# FLEX_MCU_CONFIG.net
KiCad netlist of a schematic drawn in Altium Designer
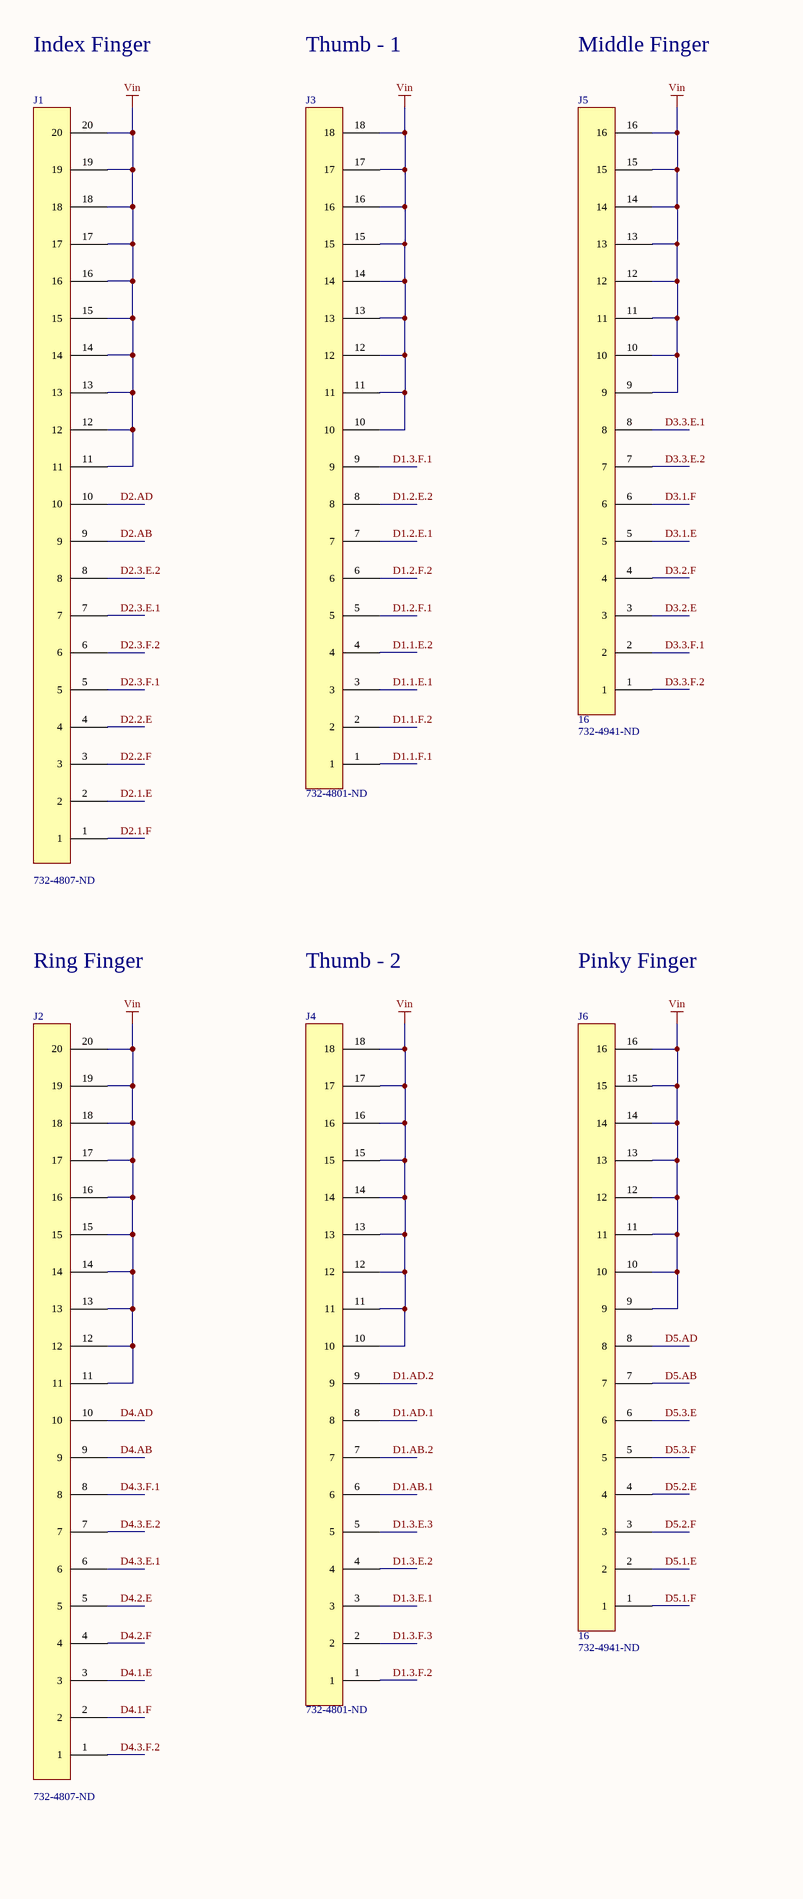
[diagram p0: FLEX_MCU_CONFIG.SchDoc, left]
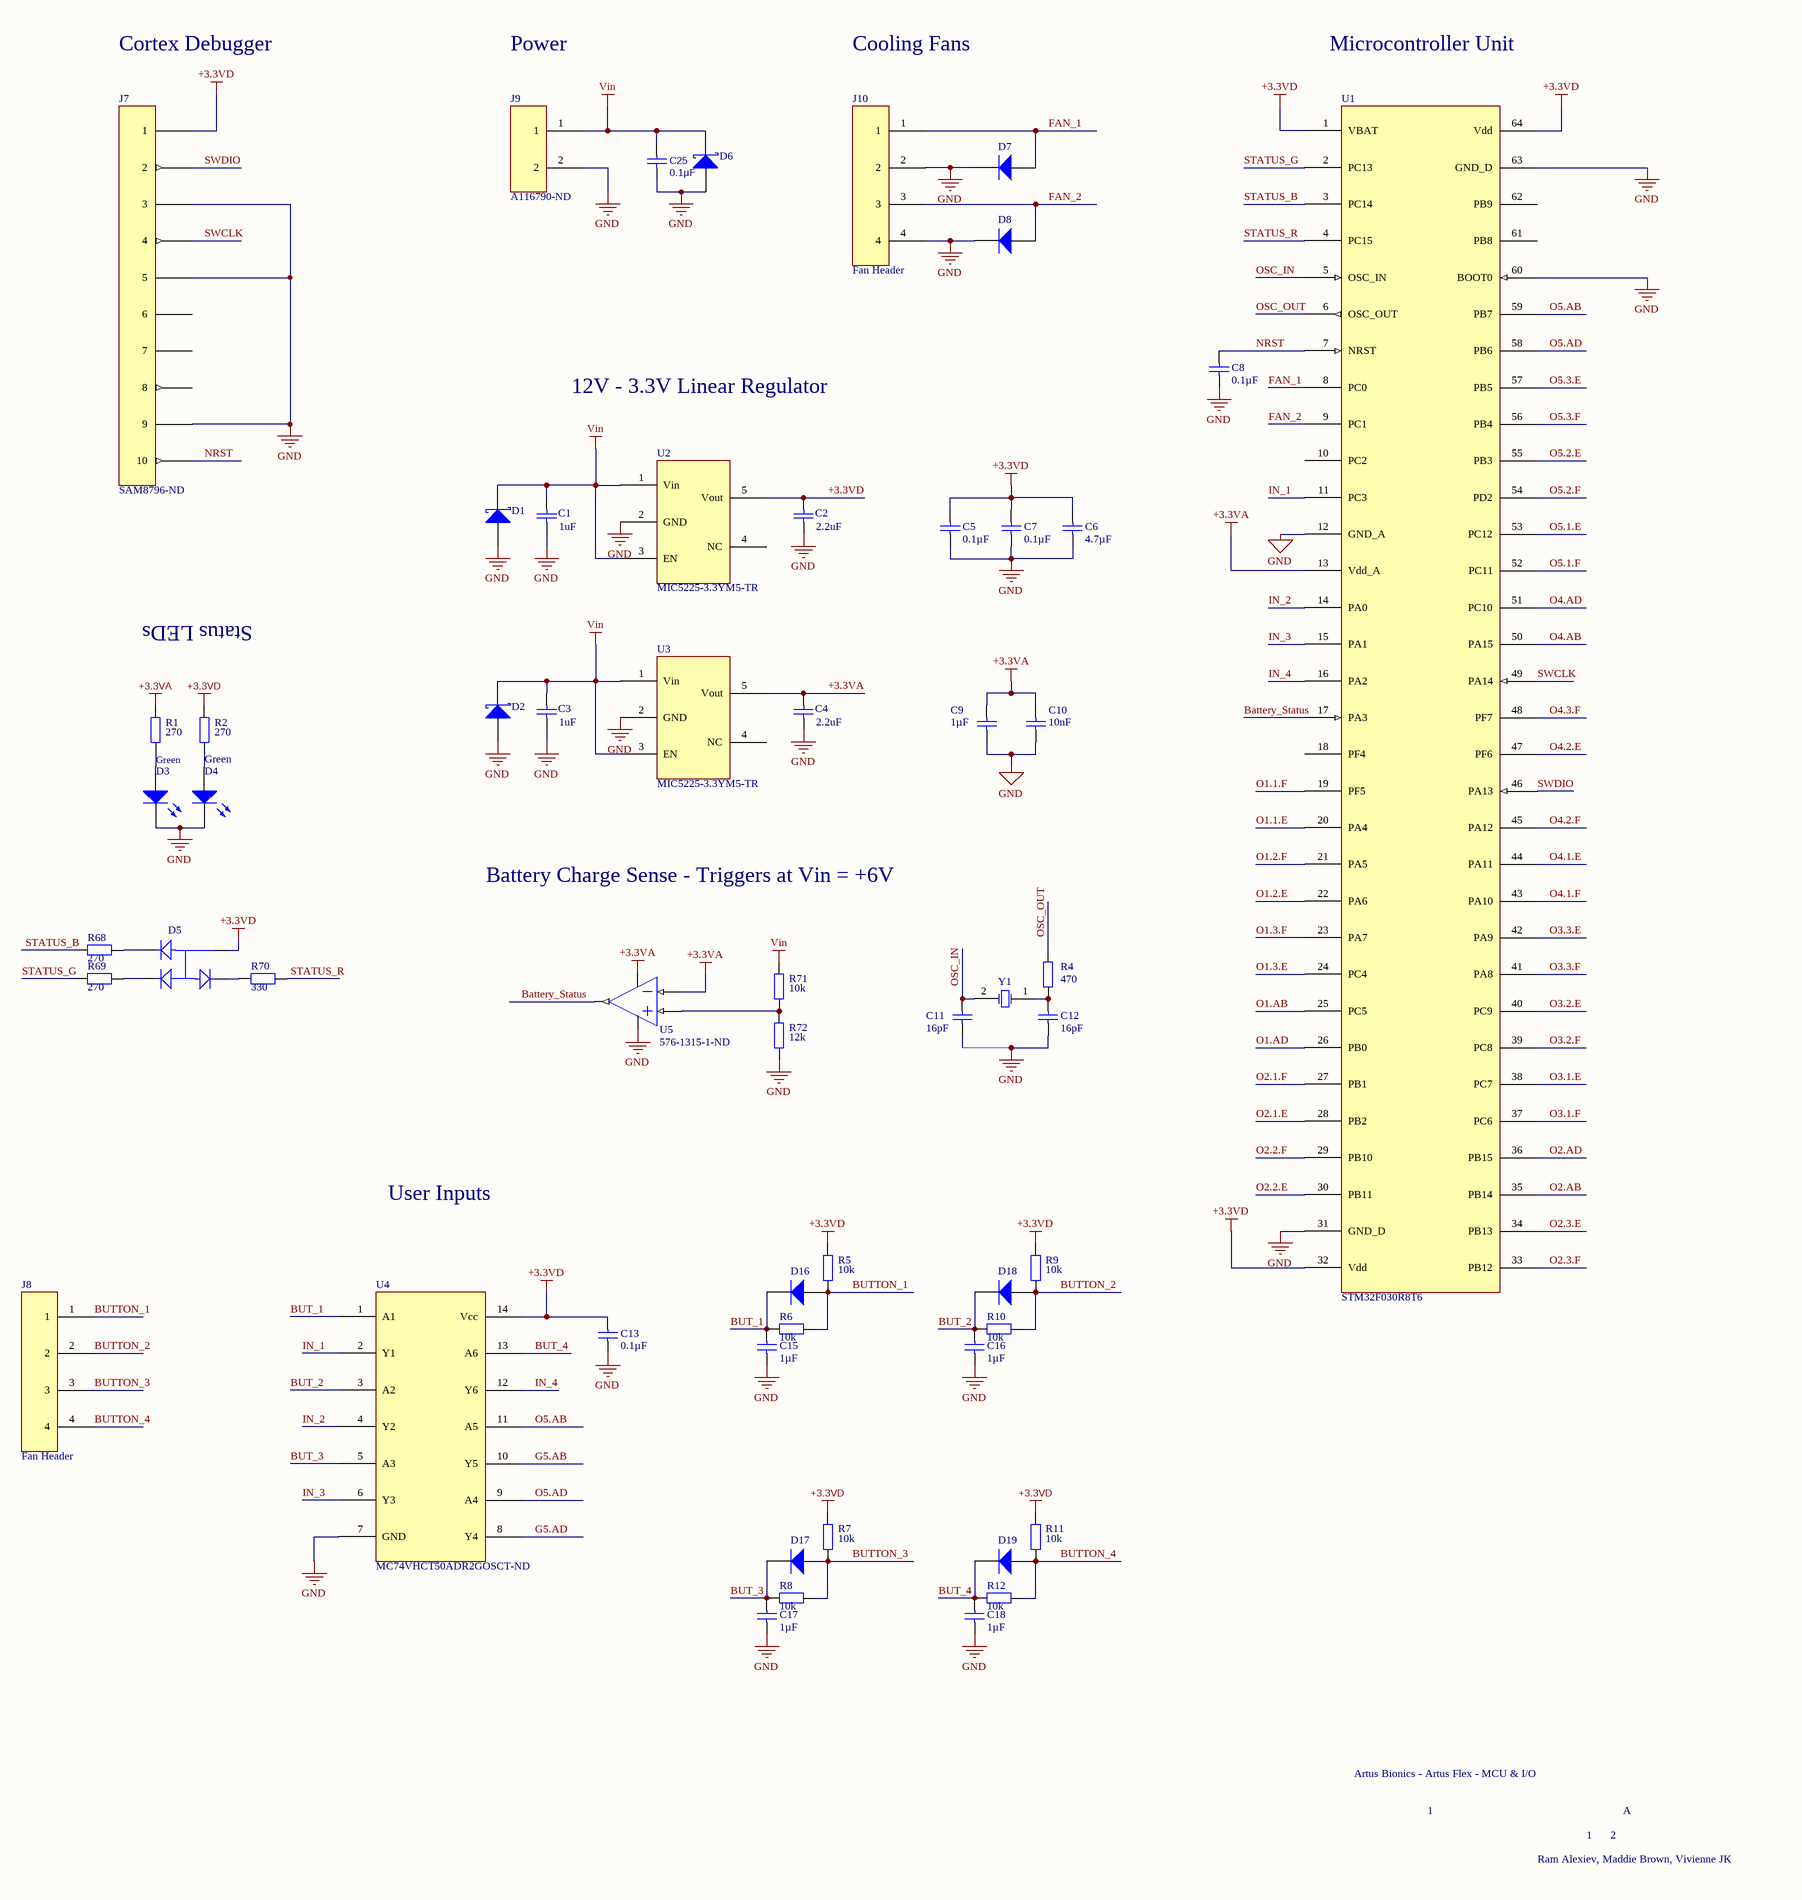
[diagram p1: FLEX_MCU_CONFIG.SchDoc, right]

(export (version "E")
  (design (tool "Eeschema 10.0.6"))
  (components
    (comp (ref "C1")
      (value "1uF")
      (footprint "TDK C-Series (1608)")
      (description "Capacitor")
      (fields (field (name "PUBLISHER") "Altium Limited"))
      (libsource (lib "Miscellaneous Devices") (part "Cap"))
    )
    (comp (ref "C2")
      (value "2.2uF")
      (footprint "TDK C-Series (1608)")
      (description "Capacitor")
      (fields (field (name "PUBLISHER") "Altium Limited"))
      (libsource (lib "Miscellaneous Devices") (part "Cap"))
    )
    (comp (ref "C3")
      (value "1uF")
      (footprint "TDK C-Series (1608)")
      (description "Capacitor")
      (fields (field (name "PUBLISHER") "Altium Limited"))
      (libsource (lib "Miscellaneous Devices") (part "Cap"))
    )
    (comp (ref "C4")
      (value "2.2uF")
      (footprint "TDK C-Series (1608)")
      (description "Capacitor")
      (fields (field (name "PUBLISHER") "Altium Limited"))
      (libsource (lib "Miscellaneous Devices") (part "Cap"))
    )
    (comp (ref "C5")
      (value "0.1µF")
      (footprint "TDK C-Series (1608)")
      (description "Capacitor")
      (fields (field (name "PUBLISHER") "Altium Limited"))
      (libsource (lib "Miscellaneous Devices") (part "Cap"))
    )
    (comp (ref "C6")
      (value "4.7µF")
      (footprint "TDK C-Series (1608)")
      (description "Capacitor")
      (fields (field (name "Comment") "Cap") (field (name "PUBLISHER") "Altium Limited"))
      (libsource (lib "Miscellaneous Devices") (part "Cap"))
    )
    (comp (ref "C7")
      (value "0.1µF")
      (footprint "TDK C-Series (1608)")
      (description "Capacitor")
      (fields (field (name "PUBLISHER") "Altium Limited"))
      (libsource (lib "Miscellaneous Devices") (part "Cap"))
    )
    (comp (ref "C8")
      (value "0.1µF")
      (footprint "TDK C-Series (1608)")
      (description "Capacitor")
      (fields (field (name "PUBLISHER") "Altium Limited"))
      (libsource (lib "Miscellaneous Devices") (part "Cap"))
    )
    (comp (ref "C9")
      (value "1µF")
      (footprint "TDK C-Series (1608)")
      (description "Capacitor")
      (fields (field (name "PUBLISHER") "Altium Limited"))
      (libsource (lib "Miscellaneous Devices") (part "Cap"))
    )
    (comp (ref "C10")
      (value "10nF")
      (footprint "TDK C-Series (1608)")
      (description "Capacitor")
      (fields (field (name "PUBLISHER") "Altium Limited"))
      (libsource (lib "Miscellaneous Devices") (part "Cap"))
    )
    (comp (ref "C11")
      (value "16pF")
      (footprint "Johanson S-Series (1608)")
      (description "Capacitor")
      (fields (field (name "PUBLISHER") "Altium Limited"))
      (libsource (lib "Miscellaneous Devices") (part "Cap"))
    )
    (comp (ref "C12")
      (value "16pF")
      (footprint "Johanson S-Series (1608)")
      (description "Capacitor")
      (fields (field (name "PUBLISHER") "Altium Limited"))
      (libsource (lib "Miscellaneous Devices") (part "Cap"))
    )
    (comp (ref "C13")
      (value "0.1µF")
      (footprint "TDK C-Series (1608)")
      (description "Capacitor")
      (fields (field (name "Comment") "Cap") (field (name "PUBLISHER") "Altium Limited"))
      (libsource (lib "Miscellaneous Devices") (part "Cap"))
    )
    (comp (ref "C15")
      (value "1µF")
      (footprint "TDK C-Series (1608)")
      (description "Capacitor")
      (fields (field (name "Comment") "Cap") (field (name "PUBLISHER") "Altium Limited"))
      (libsource (lib "Miscellaneous Devices") (part "Cap"))
    )
    (comp (ref "C16")
      (value "1µF")
      (footprint "TDK C-Series (1608)")
      (description "Capacitor")
      (fields (field (name "Comment") "Cap") (field (name "PUBLISHER") "Altium Limited"))
      (libsource (lib "Miscellaneous Devices") (part "Cap"))
    )
    (comp (ref "C17")
      (value "1µF")
      (footprint "TDK C-Series (1608)")
      (description "Capacitor")
      (fields (field (name "Comment") "Cap") (field (name "PUBLISHER") "Altium Limited"))
      (libsource (lib "Miscellaneous Devices") (part "Cap"))
    )
    (comp (ref "C18")
      (value "1µF")
      (footprint "TDK C-Series (1608)")
      (description "Capacitor")
      (fields (field (name "Comment") "Cap") (field (name "PUBLISHER") "Altium Limited"))
      (libsource (lib "Miscellaneous Devices") (part "Cap"))
    )
    (comp (ref "C25")
      (value "0.1µF")
      (footprint "TDK C-Series (1608)")
      (description "Capacitor")
      (fields (field (name "PUBLISHER") "Altium Limited"))
      (libsource (lib "Miscellaneous Devices") (part "Cap"))
    )
    (comp (ref "D1")
      (value "~")
      (footprint "Diode_TVS")
      (description "Schottky Rectifier")
      (fields (field (name "PUBLISHER") "Altium Limited"))
      (libsource (lib "Miscellaneous Devices") (part "Diode 10TQ035"))
    )
    (comp (ref "D2")
      (value "~")
      (footprint "Diode_TVS")
      (description "Schottky Rectifier")
      (fields (field (name "PUBLISHER") "Altium Limited"))
      (libsource (lib "Miscellaneous Devices") (part "Diode 10TQ035"))
    )
    (comp (ref "D3")
      (value "LTST-C193KGKT-5A")
      (footprint "Lite-On LTST-C193K-Series (1608)")
      (description "Typical INFRARED GaAs LED")
      (fields (field (name "PUBLISHER") "Altium Limited"))
      (libsource (lib "Miscellaneous Devices") (part "LED0"))
    )
    (comp (ref "D4")
      (value "LTST-C193KGKT-5A")
      (footprint "Lite-On LTST-C193K-Series (1608)")
      (description "Typical INFRARED GaAs LED")
      (fields (field (name "PUBLISHER") "Altium Limited"))
      (libsource (lib "Miscellaneous Devices") (part "LED0"))
    )
    (comp (ref "D5")
      (value "Cree CLVBA-FKA-CAEDH8BBB7A363")
      (footprint "Cree CLVBA-FKA-Series (4-SOJ)")
      (description "RGB LED")
      (libsource (lib "BMS_2017 Core") (part "Cree CLVBA-FKA-CAEDH8BBB7A363"))
    )
    (comp (ref "D6")
      (value "Diode BAT17")
      (footprint "Diode_TVS")
      (description "Silicon RF Schottky Diode for Mixer Applications in the VHF/UHF Range")
      (fields (field (name "PUBLISHER") "Altium Limited"))
      (libsource (lib "Miscellaneous Devices") (part "Diode BAT17"))
    )
    (comp (ref "D7")
      (value "Diode 1N4006")
      (footprint "Diode_Shottky")
      (description "1 Amp General Purpose Rectifier")
      (fields (field (name "PUBLISHER") "Altium Limited"))
      (libsource (lib "Miscellaneous Devices") (part "Diode 1N4006"))
    )
    (comp (ref "D8")
      (value "Diode 1N4006")
      (footprint "Diode_Shottky")
      (description "1 Amp General Purpose Rectifier")
      (fields (field (name "PUBLISHER") "Altium Limited"))
      (libsource (lib "Miscellaneous Devices") (part "Diode 1N4006"))
    )
    (comp (ref "D16")
      (value "de")
      (footprint "Diode_Shottky")
      (description "Default Diode")
      (fields (field (name "PUBLISHER") "Altium Limited"))
      (libsource (lib "Miscellaneous Devices") (part "Diode"))
    )
    (comp (ref "D17")
      (value "de")
      (footprint "Diode_Shottky")
      (description "Default Diode")
      (fields (field (name "PUBLISHER") "Altium Limited"))
      (libsource (lib "Miscellaneous Devices") (part "Diode"))
    )
    (comp (ref "D18")
      (value "de")
      (footprint "Diode_Shottky")
      (description "Default Diode")
      (fields (field (name "PUBLISHER") "Altium Limited"))
      (libsource (lib "Miscellaneous Devices") (part "Diode"))
    )
    (comp (ref "D19")
      (value "de")
      (footprint "Diode_Shottky")
      (description "Default Diode")
      (fields (field (name "PUBLISHER") "Altium Limited"))
      (libsource (lib "Miscellaneous Devices") (part "Diode"))
    )
    (comp (ref "J1")
      (value "20 Pin Header")
      (footprint "20PIN_UP_CONNECTOR")
      (description "20 position header")
      (fields (field (name "SUPPLIER PART NUMBER 1") "732-4807-ND"))
      (libsource (lib "Schematics Library") (part "20 Pin Header"))
    )
    (comp (ref "J2")
      (value "20 Pin Header")
      (footprint "20PIN_UP_CONNECTOR")
      (description "20 position header")
      (fields (field (name "SUPPLIER PART NUMBER 1") "732-4807-ND"))
      (libsource (lib "Schematics Library") (part "20 Pin Header"))
    )
    (comp (ref "J3")
      (value "18 Pin Header")
      (footprint "18PIN_UP_CONNECTOR")
      (description "18 Position Header")
      (fields (field (name "SUPPLIER PART NUMBER 1") "732-4801-ND"))
      (libsource (lib "Schematics Library") (part "18 Pin Header"))
    )
    (comp (ref "J4")
      (value "18 Pin Header")
      (footprint "18PIN_UP_CONNECTOR")
      (description "18 Position Header")
      (fields (field (name "SUPPLIER PART NUMBER 1") "732-4801-ND"))
      (libsource (lib "Schematics Library") (part "18 Pin Header"))
    )
    (comp (ref "J5")
      (value "16")
      (description "16 Position header")
      (fields (field (name "SUPPLIER PART NUMBER 1") "732-4941-ND"))
      (libsource (lib "Schematics Library") (part "16"))
    )
    (comp (ref "J6")
      (value "16")
      (description "16 Position header")
      (fields (field (name "SUPPLIER PART NUMBER 1") "732-4941-ND"))
      (libsource (lib "Schematics Library") (part "16"))
    )
    (comp (ref "J7")
      (value "Cortex Debugger")
      (footprint "Samtec FTSH-105-01-L-DV-K")
      (description "Header")
      (fields (field (name "SUPPLIER PART NUMBER 2") "SAM8796-ND"))
      (libsource (lib "Schematics Library") (part "Cortex Debugger"))
    )
    (comp (ref "J8") (value "Fan Header") (libsource (lib "Schematics Library") (part "Fan Header")))
    (comp (ref "J9")
      (value "Power Header")
      (footprint "2PIN_TERMINAL_BLOCK")
      (fields (field (name "SUPPLIER PART NUMBER 1") "A116790-ND"))
      (libsource (lib "Schematics Library") (part "Power Header"))
    )
    (comp (ref "J10") (value "Fan Header") (libsource (lib "Schematics Library") (part "Fan Header")))
    (comp (ref "R1")
      (value "270")
      (footprint "Panasonic ERJ-Series (1608)")
      (description "Resistor")
      (fields (field (name "PUBLISHER") "Altium Limited"))
      (libsource (lib "Miscellaneous Devices") (part "Res2"))
    )
    (comp (ref "R2")
      (value "270")
      (footprint "Panasonic ERJ-Series (1608)")
      (description "Resistor")
      (fields (field (name "PUBLISHER") "Altium Limited"))
      (libsource (lib "Miscellaneous Devices") (part "Res2"))
    )
    (comp (ref "R4")
      (value "470")
      (footprint "Panasonic ERJ-Series (1608)")
      (description "Resistor")
      (fields (field (name "PUBLISHER") "Altium Limited"))
      (libsource (lib "Miscellaneous Devices") (part "Res2"))
    )
    (comp (ref "R5")
      (value "10k")
      (footprint "Panasonic ERJ-Series (1608)")
      (description "Resistor")
      (fields (field (name "PUBLISHER") "Altium Limited"))
      (libsource (lib "") (part "Res2_1"))
    )
    (comp (ref "R6")
      (value "10k")
      (footprint "Panasonic ERJ-Series (1608)")
      (description "Resistor")
      (fields (field (name "PUBLISHER") "Altium Limited"))
      (libsource (lib "Miscellaneous Devices") (part "Res2"))
    )
    (comp (ref "R7")
      (value "10k")
      (footprint "Panasonic ERJ-Series (1608)")
      (description "Resistor")
      (fields (field (name "PUBLISHER") "Altium Limited"))
      (libsource (lib "") (part "Res2_1"))
    )
    (comp (ref "R8")
      (value "10k")
      (footprint "Panasonic ERJ-Series (1608)")
      (description "Resistor")
      (fields (field (name "PUBLISHER") "Altium Limited"))
      (libsource (lib "Miscellaneous Devices") (part "Res2"))
    )
    (comp (ref "R9")
      (value "10k")
      (footprint "Panasonic ERJ-Series (1608)")
      (description "Resistor")
      (fields (field (name "PUBLISHER") "Altium Limited"))
      (libsource (lib "") (part "Res2_1"))
    )
    (comp (ref "R10")
      (value "10k")
      (footprint "Panasonic ERJ-Series (1608)")
      (description "Resistor")
      (fields (field (name "PUBLISHER") "Altium Limited"))
      (libsource (lib "Miscellaneous Devices") (part "Res2"))
    )
    (comp (ref "R11")
      (value "10k")
      (footprint "Panasonic ERJ-Series (1608)")
      (description "Resistor")
      (fields (field (name "PUBLISHER") "Altium Limited"))
      (libsource (lib "") (part "Res2_1"))
    )
    (comp (ref "R12")
      (value "10k")
      (footprint "Panasonic ERJ-Series (1608)")
      (description "Resistor")
      (fields (field (name "PUBLISHER") "Altium Limited"))
      (libsource (lib "Miscellaneous Devices") (part "Res2"))
    )
    (comp (ref "R68")
      (value "270")
      (footprint "Panasonic ERJ-Series (1608)")
      (description "Resistor")
      (fields (field (name "PUBLISHER") "Altium Limited"))
      (libsource (lib "") (part "Res2_2"))
    )
    (comp (ref "R69")
      (value "270")
      (footprint "Panasonic ERJ-Series (1608)")
      (description "Resistor")
      (fields (field (name "PUBLISHER") "Altium Limited"))
      (libsource (lib "") (part "Res2_2"))
    )
    (comp (ref "R70")
      (value "330")
      (footprint "Panasonic ERJ-Series (1608)")
      (description "Resistor")
      (fields (field (name "PUBLISHER") "Altium Limited"))
      (libsource (lib "") (part "Res2_2"))
    )
    (comp (ref "R71")
      (value "10k")
      (footprint "Panasonic ERJ-Series (1608)")
      (description "Resistor")
      (fields (field (name "PUBLISHER") "Altium Limited"))
      (libsource (lib "") (part "Res2_1"))
    )
    (comp (ref "R72")
      (value "12k")
      (footprint "Panasonic ERJ-Series (1608)")
      (description "Resistor")
      (fields (field (name "PUBLISHER") "Altium Limited"))
      (libsource (lib "") (part "Res2_1"))
    )
    (comp (ref "U1")
      (value "STM32F030R8T6")
      (description "MCU")
      (libsource (lib "Schematics Library") (part "STM32F030R8T6"))
    )
    (comp (ref "U2")
      (value "MIC5225-3.3YM5-TR")
      (footprint "LINEAR REGULATOR SOT95P280X145-5N")
      (description "12V-3.3V Linear Regulator")
      (libsource (lib "Schematics Library") (part "MIC5225-3.3YM5-TR"))
    )
    (comp (ref "U3")
      (value "MIC5225-3.3YM5-TR")
      (footprint "LINEAR REGULATOR SOT95P280X145-5N")
      (description "12V-3.3V Linear Regulator")
      (libsource (lib "Schematics Library") (part "MIC5225-3.3YM5-TR"))
    )
    (comp (ref "U4")
      (value "MC74VHCT50A")
      (description "6-Channel CMOS Buffer")
      (fields (field (name "SUPPLIER PART NUMBER 1") "MC74VHCT50ADR2GOSCT-ND"))
      (libsource (lib "Schematics Library") (part "MC74VHCT50A"))
    )
    (comp (ref "U5")
      (value "TSV991ILT")
      (footprint "LINEAR REGULATOR SOT95P280X145-5N")
      (description "20MHz Op-Amp")
      (fields (field (name "SUPPLIER PART NUMBER 1") "576-1315-1-ND"))
      (libsource (lib "FSM_2017") (part "STMicroelectronics TSV991ILT"))
    )
    (comp (ref "Y1")
      (value "~")
      (footprint "Abracon ABM3-8.000MHZ-D2Y-T (2-DFN)")
      (description "Crystal Oscillator")
      (fields (field (name "PUBLISHER") "Altium Limited"))
      (libsource (lib "Miscellaneous Devices") (part "XTAL"))
    )
  )
  (nets
    (net (code "1") (name "+3.3VA") (class "Default")
      (node (ref "C10") (pin "2") (pinfunction "2_2") (pintype "passive"))
      (node (ref "C4") (pin "2") (pinfunction "2_2") (pintype "passive"))
      (node (ref "C9") (pin "2") (pinfunction "2_2") (pintype "passive"))
      (node (ref "R1") (pin "2") (pinfunction "2_2") (pintype "passive"))
      (node (ref "U1") (pin "13") (pinfunction "Vdd_A_13") (pintype "power_in"))
      (node (ref "U3") (pin "5") (pinfunction "Vout_5") (pintype "passive"))
      (node (ref "U5") (pin "2") (pinfunction "VCC-_2") (pintype "power_in"))
      (node (ref "U5") (pin "4") (pinfunction "IN-_4") (pintype "input"))
    )
    (net (code "2") (name "+3.3VD") (class "Default")
      (node (ref "C13") (pin "2") (pinfunction "2_2") (pintype "passive"))
      (node (ref "C2") (pin "2") (pinfunction "2_2") (pintype "passive"))
      (node (ref "C5") (pin "2") (pinfunction "2_2") (pintype "passive"))
      (node (ref "C6") (pin "2") (pinfunction "2_2") (pintype "passive"))
      (node (ref "C7") (pin "2") (pinfunction "2_2") (pintype "passive"))
      (node (ref "D5") (pin "2") (pinfunction "COMMON_ANODE_2") (pintype "passive"))
      (node (ref "J7") (pin "1") (pinfunction "1_1") (pintype "power_in"))
      (node (ref "R11") (pin "1") (pinfunction "1_1") (pintype "passive"))
      (node (ref "R2") (pin "2") (pinfunction "2_2") (pintype "passive"))
      (node (ref "R5") (pin "1") (pinfunction "1_1") (pintype "passive"))
      (node (ref "R7") (pin "1") (pinfunction "1_1") (pintype "passive"))
      (node (ref "R9") (pin "1") (pinfunction "1_1") (pintype "passive"))
      (node (ref "U1") (pin "1") (pinfunction "VBAT_1") (pintype "power_in"))
      (node (ref "U1") (pin "32") (pinfunction "Vdd_32") (pintype "power_in"))
      (node (ref "U1") (pin "64") (pinfunction "Vdd_64") (pintype "power_in"))
      (node (ref "U2") (pin "5") (pinfunction "Vout_5") (pintype "passive"))
      (node (ref "U4") (pin "14") (pinfunction "Vcc_14") (pintype "power_in"))
    )
    (net (code "3") (name "/BUTTON_1") (class "Default")
      (node (ref "D16") (pin "1") (pinfunction "A_1") (pintype "passive"))
      (node (ref "J8") (pin "1") (pinfunction "1_1") (pintype "power_in"))
      (node (ref "R5") (pin "2") (pinfunction "2_2") (pintype "passive"))
      (node (ref "R6") (pin "2") (pinfunction "2_2") (pintype "passive"))
    )
    (net (code "4") (name "/BUTTON_2") (class "Default")
      (node (ref "D18") (pin "1") (pinfunction "A_1") (pintype "passive"))
      (node (ref "J8") (pin "2") (pinfunction "2_2") (pintype "power_in"))
      (node (ref "R10") (pin "2") (pinfunction "2_2") (pintype "passive"))
      (node (ref "R9") (pin "2") (pinfunction "2_2") (pintype "passive"))
    )
    (net (code "5") (name "/BUTTON_3") (class "Default")
      (node (ref "D17") (pin "1") (pinfunction "A_1") (pintype "passive"))
      (node (ref "J8") (pin "3") (pinfunction "3_3") (pintype "power_in"))
      (node (ref "R7") (pin "2") (pinfunction "2_2") (pintype "passive"))
      (node (ref "R8") (pin "2") (pinfunction "2_2") (pintype "passive"))
    )
    (net (code "6") (name "/BUTTON_4") (class "Default")
      (node (ref "D19") (pin "1") (pinfunction "A_1") (pintype "passive"))
      (node (ref "J8") (pin "4") (pinfunction "4_4") (pintype "power_in"))
      (node (ref "R11") (pin "2") (pinfunction "2_2") (pintype "passive"))
      (node (ref "R12") (pin "2") (pinfunction "2_2") (pintype "passive"))
    )
    (net (code "7") (name "/BUT_1") (class "Default")
      (node (ref "C15") (pin "2") (pinfunction "2_2") (pintype "passive"))
      (node (ref "D16") (pin "2") (pinfunction "K_2") (pintype "passive"))
      (node (ref "R6") (pin "1") (pinfunction "1_1") (pintype "passive"))
      (node (ref "U4") (pin "1") (pinfunction "A1_1") (pintype "power_in"))
    )
    (net (code "8") (name "/BUT_2") (class "Default")
      (node (ref "C16") (pin "2") (pinfunction "2_2") (pintype "passive"))
      (node (ref "D18") (pin "2") (pinfunction "K_2") (pintype "passive"))
      (node (ref "R10") (pin "1") (pinfunction "1_1") (pintype "passive"))
      (node (ref "U4") (pin "3") (pinfunction "A2_3") (pintype "power_in"))
    )
    (net (code "9") (name "/BUT_3") (class "Default")
      (node (ref "C17") (pin "2") (pinfunction "2_2") (pintype "passive"))
      (node (ref "D17") (pin "2") (pinfunction "K_2") (pintype "passive"))
      (node (ref "R8") (pin "1") (pinfunction "1_1") (pintype "passive"))
      (node (ref "U4") (pin "5") (pinfunction "A3_5") (pintype "power_in"))
    )
    (net (code "10") (name "/BUT_4") (class "Default")
      (node (ref "C18") (pin "2") (pinfunction "2_2") (pintype "passive"))
      (node (ref "D19") (pin "2") (pinfunction "K_2") (pintype "passive"))
      (node (ref "R12") (pin "1") (pinfunction "1_1") (pintype "passive"))
      (node (ref "U4") (pin "13") (pinfunction "A6_13") (pintype "power_in"))
    )
    (net (code "11") (name "/Battery_Status") (class "Default")
      (node (ref "U1") (pin "17") (pinfunction "PA3_17") (pintype "input"))
      (node (ref "U5") (pin "1") (pinfunction "OUT_1") (pintype "output"))
    )
    (net (code "12") (name "/D1.1.E.1") (class "Default")
      (node (ref "J3") (pin "3") (pinfunction "3_3") (pintype "power_in"))
    )
    (net (code "13") (name "/D1.1.E.2") (class "Default")
      (node (ref "J3") (pin "4") (pinfunction "4_4") (pintype "power_in"))
    )
    (net (code "14") (name "/D1.1.F.1") (class "Default")
      (node (ref "J3") (pin "1") (pinfunction "1_1") (pintype "power_in"))
    )
    (net (code "15") (name "/D1.1.F.2") (class "Default")
      (node (ref "J3") (pin "2") (pinfunction "2_2") (pintype "power_in"))
    )
    (net (code "16") (name "/D1.2.E.1") (class "Default")
      (node (ref "J3") (pin "7") (pinfunction "7_7") (pintype "power_in"))
    )
    (net (code "17") (name "/D1.2.E.2") (class "Default")
      (node (ref "J3") (pin "8") (pinfunction "8_8") (pintype "power_in"))
    )
    (net (code "18") (name "/D1.2.F.1") (class "Default")
      (node (ref "J3") (pin "5") (pinfunction "5_5") (pintype "power_in"))
    )
    (net (code "19") (name "/D1.2.F.2") (class "Default")
      (node (ref "J3") (pin "6") (pinfunction "6_6") (pintype "power_in"))
    )
    (net (code "20") (name "/D1.3.E.1") (class "Default")
      (node (ref "J4") (pin "3") (pinfunction "3_3") (pintype "power_in"))
    )
    (net (code "21") (name "/D1.3.E.2") (class "Default")
      (node (ref "J4") (pin "4") (pinfunction "4_4") (pintype "power_in"))
    )
    (net (code "22") (name "/D1.3.E.3") (class "Default")
      (node (ref "J4") (pin "5") (pinfunction "5_5") (pintype "power_in"))
    )
    (net (code "23") (name "/D1.3.F.1") (class "Default")
      (node (ref "J3") (pin "9") (pinfunction "9_9") (pintype "power_in"))
    )
    (net (code "24") (name "/D1.3.F.2") (class "Default")
      (node (ref "J4") (pin "1") (pinfunction "1_1") (pintype "power_in"))
    )
    (net (code "25") (name "/D1.3.F.3") (class "Default")
      (node (ref "J4") (pin "2") (pinfunction "2_2") (pintype "power_in"))
    )
    (net (code "26") (name "/D1.AB.1") (class "Default")
      (node (ref "J4") (pin "6") (pinfunction "6_6") (pintype "power_in"))
    )
    (net (code "27") (name "/D1.AB.2") (class "Default")
      (node (ref "J4") (pin "7") (pinfunction "7_7") (pintype "power_in"))
    )
    (net (code "28") (name "/D1.AD.1") (class "Default")
      (node (ref "J4") (pin "8") (pinfunction "8_8") (pintype "power_in"))
    )
    (net (code "29") (name "/D1.AD.2") (class "Default")
      (node (ref "J4") (pin "9") (pinfunction "9_9") (pintype "power_in"))
    )
    (net (code "30") (name "/D2.1.E") (class "Default")
      (node (ref "J1") (pin "2") (pinfunction "2_2") (pintype "power_in"))
    )
    (net (code "31") (name "/D2.1.F") (class "Default")
      (node (ref "J1") (pin "1") (pinfunction "1_1") (pintype "power_in"))
    )
    (net (code "32") (name "/D2.2.E") (class "Default")
      (node (ref "J1") (pin "4") (pinfunction "4_4") (pintype "power_in"))
    )
    (net (code "33") (name "/D2.2.F") (class "Default")
      (node (ref "J1") (pin "3") (pinfunction "3_3") (pintype "power_in"))
    )
    (net (code "34") (name "/D2.3.E.1") (class "Default")
      (node (ref "J1") (pin "7") (pinfunction "7_7") (pintype "power_in"))
    )
    (net (code "35") (name "/D2.3.E.2") (class "Default")
      (node (ref "J1") (pin "8") (pinfunction "8_8") (pintype "power_in"))
    )
    (net (code "36") (name "/D2.3.F.1") (class "Default")
      (node (ref "J1") (pin "5") (pinfunction "5_5") (pintype "power_in"))
    )
    (net (code "37") (name "/D2.3.F.2") (class "Default")
      (node (ref "J1") (pin "6") (pinfunction "6_6") (pintype "power_in"))
    )
    (net (code "38") (name "/D2.AB") (class "Default")
      (node (ref "J1") (pin "9") (pinfunction "9_9") (pintype "power_in"))
    )
    (net (code "39") (name "/D2.AD") (class "Default")
      (node (ref "J1") (pin "10") (pinfunction "10_10") (pintype "power_in"))
    )
    (net (code "40") (name "/D3.1.E") (class "Default")
      (node (ref "J5") (pin "5") (pinfunction "5_5") (pintype "power_in"))
    )
    (net (code "41") (name "/D3.1.F") (class "Default")
      (node (ref "J5") (pin "6") (pinfunction "6_6") (pintype "power_in"))
    )
    (net (code "42") (name "/D3.2.E") (class "Default")
      (node (ref "J5") (pin "3") (pinfunction "3_3") (pintype "power_in"))
    )
    (net (code "43") (name "/D3.2.F") (class "Default")
      (node (ref "J5") (pin "4") (pinfunction "4_4") (pintype "power_in"))
    )
    (net (code "44") (name "/D3.3.E.1") (class "Default")
      (node (ref "J5") (pin "8") (pinfunction "8_8") (pintype "power_in"))
    )
    (net (code "45") (name "/D3.3.E.2") (class "Default")
      (node (ref "J5") (pin "7") (pinfunction "7_7") (pintype "power_in"))
    )
    (net (code "46") (name "/D3.3.F.1") (class "Default")
      (node (ref "J5") (pin "2") (pinfunction "2_2") (pintype "power_in"))
    )
    (net (code "47") (name "/D3.3.F.2") (class "Default")
      (node (ref "J5") (pin "1") (pinfunction "1_1") (pintype "power_in"))
    )
    (net (code "48") (name "/D4.1.E") (class "Default")
      (node (ref "J2") (pin "3") (pinfunction "3_3") (pintype "power_in"))
    )
    (net (code "49") (name "/D4.1.F") (class "Default")
      (node (ref "J2") (pin "2") (pinfunction "2_2") (pintype "power_in"))
    )
    (net (code "50") (name "/D4.2.E") (class "Default")
      (node (ref "J2") (pin "5") (pinfunction "5_5") (pintype "power_in"))
    )
    (net (code "51") (name "/D4.2.F") (class "Default")
      (node (ref "J2") (pin "4") (pinfunction "4_4") (pintype "power_in"))
    )
    (net (code "52") (name "/D4.3.E.1") (class "Default")
      (node (ref "J2") (pin "6") (pinfunction "6_6") (pintype "power_in"))
    )
    (net (code "53") (name "/D4.3.E.2") (class "Default")
      (node (ref "J2") (pin "7") (pinfunction "7_7") (pintype "power_in"))
    )
    (net (code "54") (name "/D4.3.F.1") (class "Default")
      (node (ref "J2") (pin "8") (pinfunction "8_8") (pintype "power_in"))
    )
    (net (code "55") (name "/D4.3.F.2") (class "Default")
      (node (ref "J2") (pin "1") (pinfunction "1_1") (pintype "power_in"))
    )
    (net (code "56") (name "/D4.AB") (class "Default")
      (node (ref "J2") (pin "9") (pinfunction "9_9") (pintype "power_in"))
    )
    (net (code "57") (name "/D4.AD") (class "Default")
      (node (ref "J2") (pin "10") (pinfunction "10_10") (pintype "power_in"))
    )
    (net (code "58") (name "/D5.1.E") (class "Default")
      (node (ref "J6") (pin "2") (pinfunction "2_2") (pintype "power_in"))
    )
    (net (code "59") (name "/D5.1.F") (class "Default")
      (node (ref "J6") (pin "1") (pinfunction "1_1") (pintype "power_in"))
    )
    (net (code "60") (name "/D5.2.E") (class "Default")
      (node (ref "J6") (pin "4") (pinfunction "4_4") (pintype "power_in"))
    )
    (net (code "61") (name "/D5.2.F") (class "Default")
      (node (ref "J6") (pin "3") (pinfunction "3_3") (pintype "power_in"))
    )
    (net (code "62") (name "/D5.3.E") (class "Default")
      (node (ref "J6") (pin "6") (pinfunction "6_6") (pintype "power_in"))
    )
    (net (code "63") (name "/D5.3.F") (class "Default")
      (node (ref "J6") (pin "5") (pinfunction "5_5") (pintype "power_in"))
    )
    (net (code "64") (name "/D5.AB") (class "Default")
      (node (ref "J6") (pin "7") (pinfunction "7_7") (pintype "power_in"))
    )
    (net (code "65") (name "/D5.AD") (class "Default")
      (node (ref "J6") (pin "8") (pinfunction "8_8") (pintype "power_in"))
    )
    (net (code "66") (name "/FAN_1") (class "Default")
      (node (ref "D7") (pin "1") (pinfunction "A_1") (pintype "passive"))
      (node (ref "J10") (pin "1") (pinfunction "1_1") (pintype "power_in"))
      (node (ref "U1") (pin "8") (pinfunction "PC0_8") (pintype "power_in"))
    )
    (net (code "67") (name "/FAN_2") (class "Default")
      (node (ref "D8") (pin "1") (pinfunction "A_1") (pintype "passive"))
      (node (ref "J10") (pin "3") (pinfunction "3_3") (pintype "power_in"))
      (node (ref "U1") (pin "9") (pinfunction "PC1_9") (pintype "power_in"))
    )
    (net (code "68") (name "/G5.AB") (class "Default")
      (node (ref "U4") (pin "10") (pinfunction "Y5_10") (pintype "power_in"))
    )
    (net (code "69") (name "/G5.AD") (class "Default")
      (node (ref "U4") (pin "8") (pinfunction "Y4_8") (pintype "power_in"))
    )
    (net (code "70") (name "/IN_1") (class "Default")
      (node (ref "U1") (pin "11") (pinfunction "PC3_11") (pintype "power_in"))
      (node (ref "U4") (pin "2") (pinfunction "Y1_2") (pintype "power_in"))
    )
    (net (code "71") (name "/IN_2") (class "Default")
      (node (ref "U1") (pin "14") (pinfunction "PA0_14") (pintype "power_in"))
      (node (ref "U4") (pin "4") (pinfunction "Y2_4") (pintype "power_in"))
    )
    (net (code "72") (name "/IN_3") (class "Default")
      (node (ref "U1") (pin "15") (pinfunction "PA1_15") (pintype "power_in"))
      (node (ref "U4") (pin "6") (pinfunction "Y3_6") (pintype "power_in"))
    )
    (net (code "73") (name "/IN_4") (class "Default")
      (node (ref "U1") (pin "16") (pinfunction "PA2_16") (pintype "power_in"))
      (node (ref "U4") (pin "12") (pinfunction "Y6_12") (pintype "power_in"))
    )
    (net (code "74") (name "/NRST") (class "Default")
      (node (ref "C8") (pin "2") (pinfunction "2_2") (pintype "passive"))
      (node (ref "J7") (pin "10") (pinfunction "10_10") (pintype "output"))
      (node (ref "U1") (pin "7") (pinfunction "NRST_7") (pintype "input"))
    )
    (net (code "75") (name "/O1.1.E") (class "Default")
      (node (ref "U1") (pin "20") (pinfunction "PA4_20") (pintype "power_in"))
    )
    (net (code "76") (name "/O1.1.F") (class "Default")
      (node (ref "U1") (pin "19") (pinfunction "PF5_19") (pintype "power_in"))
    )
    (net (code "77") (name "/O1.2.E") (class "Default")
      (node (ref "U1") (pin "22") (pinfunction "PA6_22") (pintype "power_in"))
    )
    (net (code "78") (name "/O1.2.F") (class "Default")
      (node (ref "U1") (pin "21") (pinfunction "PA5_21") (pintype "power_in"))
    )
    (net (code "79") (name "/O1.3.E") (class "Default")
      (node (ref "U1") (pin "24") (pinfunction "PC4_24") (pintype "power_in"))
    )
    (net (code "80") (name "/O1.3.F") (class "Default")
      (node (ref "U1") (pin "23") (pinfunction "PA7_23") (pintype "power_in"))
    )
    (net (code "81") (name "/O1.AB") (class "Default")
      (node (ref "U1") (pin "25") (pinfunction "PC5_25") (pintype "power_in"))
    )
    (net (code "82") (name "/O1.AD") (class "Default")
      (node (ref "U1") (pin "26") (pinfunction "PB0_26") (pintype "power_in"))
    )
    (net (code "83") (name "/O2.1.E") (class "Default")
      (node (ref "U1") (pin "28") (pinfunction "PB2_28") (pintype "power_in"))
    )
    (net (code "84") (name "/O2.1.F") (class "Default")
      (node (ref "U1") (pin "27") (pinfunction "PB1_27") (pintype "power_in"))
    )
    (net (code "85") (name "/O2.2.E") (class "Default")
      (node (ref "U1") (pin "30") (pinfunction "PB11_30") (pintype "power_in"))
    )
    (net (code "86") (name "/O2.2.F") (class "Default")
      (node (ref "U1") (pin "29") (pinfunction "PB10_29") (pintype "power_in"))
    )
    (net (code "87") (name "/O2.3.E") (class "Default")
      (node (ref "U1") (pin "34") (pinfunction "PB13_34") (pintype "power_in"))
    )
    (net (code "88") (name "/O2.3.F") (class "Default")
      (node (ref "U1") (pin "33") (pinfunction "PB12_33") (pintype "power_in"))
    )
    (net (code "89") (name "/O2.AB") (class "Default")
      (node (ref "U1") (pin "35") (pinfunction "PB14_35") (pintype "power_in"))
    )
    (net (code "90") (name "/O2.AD") (class "Default")
      (node (ref "U1") (pin "36") (pinfunction "PB15_36") (pintype "power_in"))
    )
    (net (code "91") (name "/O3.1.E") (class "Default")
      (node (ref "U1") (pin "38") (pinfunction "PC7_38") (pintype "power_in"))
    )
    (net (code "92") (name "/O3.1.F") (class "Default")
      (node (ref "U1") (pin "37") (pinfunction "PC6_37") (pintype "power_in"))
    )
    (net (code "93") (name "/O3.2.E") (class "Default")
      (node (ref "U1") (pin "40") (pinfunction "PC9_40") (pintype "power_in"))
    )
    (net (code "94") (name "/O3.2.F") (class "Default")
      (node (ref "U1") (pin "39") (pinfunction "PC8_39") (pintype "power_in"))
    )
    (net (code "95") (name "/O3.3.E") (class "Default")
      (node (ref "U1") (pin "42") (pinfunction "PA9_42") (pintype "power_in"))
    )
    (net (code "96") (name "/O3.3.F") (class "Default")
      (node (ref "U1") (pin "41") (pinfunction "PA8_41") (pintype "power_in"))
    )
    (net (code "97") (name "/O4.1.E") (class "Default")
      (node (ref "U1") (pin "44") (pinfunction "PA11_44") (pintype "power_in"))
    )
    (net (code "98") (name "/O4.1.F") (class "Default")
      (node (ref "U1") (pin "43") (pinfunction "PA10_43") (pintype "power_in"))
    )
    (net (code "99") (name "/O4.2.E") (class "Default")
      (node (ref "U1") (pin "47") (pinfunction "PF6_47") (pintype "power_in"))
    )
    (net (code "100") (name "/O4.2.F") (class "Default")
      (node (ref "U1") (pin "45") (pinfunction "PA12_45") (pintype "power_in"))
    )
    (net (code "101") (name "/O4.3.F") (class "Default")
      (node (ref "U1") (pin "48") (pinfunction "PF7_48") (pintype "power_in"))
    )
    (net (code "102") (name "/O4.AB") (class "Default")
      (node (ref "U1") (pin "50") (pinfunction "PA15_50") (pintype "power_in"))
    )
    (net (code "103") (name "/O4.AD") (class "Default")
      (node (ref "U1") (pin "51") (pinfunction "PC10_51") (pintype "power_in"))
    )
    (net (code "104") (name "/O5.1.E") (class "Default")
      (node (ref "U1") (pin "53") (pinfunction "PC12_53") (pintype "power_in"))
    )
    (net (code "105") (name "/O5.1.F") (class "Default")
      (node (ref "U1") (pin "52") (pinfunction "PC11_52") (pintype "power_in"))
    )
    (net (code "106") (name "/O5.2.E") (class "Default")
      (node (ref "U1") (pin "55") (pinfunction "PB3_55") (pintype "power_in"))
    )
    (net (code "107") (name "/O5.2.F") (class "Default")
      (node (ref "U1") (pin "54") (pinfunction "PD2_54") (pintype "power_in"))
    )
    (net (code "108") (name "/O5.3.E") (class "Default")
      (node (ref "U1") (pin "57") (pinfunction "PB5_57") (pintype "power_in"))
    )
    (net (code "109") (name "/O5.3.F") (class "Default")
      (node (ref "U1") (pin "56") (pinfunction "PB4_56") (pintype "power_in"))
    )
    (net (code "110") (name "/O5.AB") (class "Default")
      (node (ref "U1") (pin "59") (pinfunction "PB7_59") (pintype "power_in"))
      (node (ref "U4") (pin "11") (pinfunction "A5_11") (pintype "power_in"))
    )
    (net (code "111") (name "/O5.AD") (class "Default")
      (node (ref "U1") (pin "58") (pinfunction "PB6_58") (pintype "power_in"))
      (node (ref "U4") (pin "9") (pinfunction "A4_9") (pintype "power_in"))
    )
    (net (code "112") (name "/OSC_IN") (class "Default")
      (node (ref "C11") (pin "1") (pinfunction "1_1") (pintype "passive"))
      (node (ref "U1") (pin "5") (pinfunction "OSC_IN_5") (pintype "input"))
      (node (ref "Y1") (pin "2") (pinfunction "OSC2_2") (pintype "passive"))
    )
    (net (code "113") (name "/OSC_OUT") (class "Default")
      (node (ref "R4") (pin "2") (pinfunction "2_2") (pintype "passive"))
      (node (ref "U1") (pin "6") (pinfunction "OSC_OUT_6") (pintype "output"))
    )
    (net (code "114") (name "/STATUS_B") (class "Default")
      (node (ref "R68") (pin "1") (pinfunction "1_1") (pintype "passive"))
      (node (ref "U1") (pin "3") (pinfunction "PC14_3") (pintype "power_in"))
    )
    (net (code "115") (name "/STATUS_G") (class "Default")
      (node (ref "R69") (pin "1") (pinfunction "1_1") (pintype "passive"))
      (node (ref "U1") (pin "2") (pinfunction "PC13_2") (pintype "power_in"))
    )
    (net (code "116") (name "/STATUS_R") (class "Default")
      (node (ref "R70") (pin "2") (pinfunction "2_2") (pintype "passive"))
      (node (ref "U1") (pin "4") (pinfunction "PC15_4") (pintype "power_in"))
    )
    (net (code "117") (name "/SWCLK") (class "Default")
      (node (ref "J7") (pin "4") (pinfunction "4_4") (pintype "output"))
      (node (ref "U1") (pin "49") (pinfunction "PA14_49") (pintype "input"))
    )
    (net (code "118") (name "/SWDIO") (class "Default")
      (node (ref "J7") (pin "66") (pinfunction "2_66") (pintype "output"))
      (node (ref "U1") (pin "46") (pinfunction "PA13_46") (pintype "input"))
    )
    (net (code "119") (name "GND") (class "Default")
      (node (ref "C1") (pin "1") (pinfunction "1_1") (pintype "passive"))
      (node (ref "C10") (pin "1") (pinfunction "1_1") (pintype "passive"))
      (node (ref "C11") (pin "2") (pinfunction "2_2") (pintype "passive"))
      (node (ref "C12") (pin "2") (pinfunction "2_2") (pintype "passive"))
      (node (ref "C13") (pin "1") (pinfunction "1_1") (pintype "passive"))
      (node (ref "C15") (pin "1") (pinfunction "1_1") (pintype "passive"))
      (node (ref "C16") (pin "1") (pinfunction "1_1") (pintype "passive"))
      (node (ref "C17") (pin "1") (pinfunction "1_1") (pintype "passive"))
      (node (ref "C18") (pin "1") (pinfunction "1_1") (pintype "passive"))
      (node (ref "C2") (pin "1") (pinfunction "1_1") (pintype "passive"))
      (node (ref "C25") (pin "1") (pinfunction "1_1") (pintype "passive"))
      (node (ref "C3") (pin "1") (pinfunction "1_1") (pintype "passive"))
      (node (ref "C4") (pin "1") (pinfunction "1_1") (pintype "passive"))
      (node (ref "C5") (pin "1") (pinfunction "1_1") (pintype "passive"))
      (node (ref "C6") (pin "1") (pinfunction "1_1") (pintype "passive"))
      (node (ref "C7") (pin "1") (pinfunction "1_1") (pintype "passive"))
      (node (ref "C8") (pin "1") (pinfunction "1_1") (pintype "passive"))
      (node (ref "C9") (pin "1") (pinfunction "1_1") (pintype "passive"))
      (node (ref "D1") (pin "3") (pinfunction "A_3") (pintype "passive"))
      (node (ref "D2") (pin "3") (pinfunction "A_3") (pintype "passive"))
      (node (ref "D3") (pin "2") (pinfunction "K_2") (pintype "passive"))
      (node (ref "D4") (pin "2") (pinfunction "K_2") (pintype "passive"))
      (node (ref "D6") (pin "1") (pinfunction "A_1") (pintype "passive"))
      (node (ref "D7") (pin "2") (pinfunction "K_2") (pintype "passive"))
      (node (ref "D8") (pin "2") (pinfunction "K_2") (pintype "passive"))
      (node (ref "J10") (pin "2") (pinfunction "2_2") (pintype "power_in"))
      (node (ref "J10") (pin "4") (pinfunction "4_4") (pintype "power_in"))
      (node (ref "J7") (pin "3") (pinfunction "3_3") (pintype "power_in"))
      (node (ref "J7") (pin "5") (pinfunction "5_5") (pintype "power_in"))
      (node (ref "J7") (pin "9") (pinfunction "9_9") (pintype "power_in"))
      (node (ref "J9") (pin "2") (pinfunction "2_2") (pintype "power_in"))
      (node (ref "R72") (pin "2") (pinfunction "2_2") (pintype "passive"))
      (node (ref "U1") (pin "12") (pinfunction "GND_A_12") (pintype "power_in"))
      (node (ref "U1") (pin "31") (pinfunction "GND_D_31") (pintype "power_in"))
      (node (ref "U1") (pin "60") (pinfunction "BOOT0_60") (pintype "input"))
      (node (ref "U1") (pin "63") (pinfunction "GND_D_63") (pintype "passive"))
      (node (ref "U2") (pin "2") (pinfunction "GND_2") (pintype "passive"))
      (node (ref "U3") (pin "2") (pinfunction "GND_2") (pintype "passive"))
      (node (ref "U4") (pin "7") (pinfunction "GND_7") (pintype "power_in"))
      (node (ref "U5") (pin "5") (pinfunction "VCC+_5") (pintype "power_in"))
    )
    (net (code "120") (name "Net-(D3-A)") (class "Default")
      (node (ref "D3") (pin "1") (pinfunction "A_1") (pintype "passive"))
      (node (ref "R1") (pin "1") (pinfunction "1_1") (pintype "passive"))
    )
    (net (code "121") (name "Net-(D4-A)") (class "Default")
      (node (ref "D4") (pin "1") (pinfunction "A_1") (pintype "passive"))
      (node (ref "R2") (pin "1") (pinfunction "1_1") (pintype "passive"))
    )
    (net (code "122") (name "Net-(D5-BLUE)") (class "Default")
      (node (ref "D5") (pin "3") (pinfunction "BLUE_3") (pintype "passive"))
      (node (ref "R68") (pin "2") (pinfunction "2_2") (pintype "passive"))
    )
    (net (code "123") (name "Net-(D5-GREEN)") (class "Default")
      (node (ref "D5") (pin "4") (pinfunction "GREEN_4") (pintype "passive"))
      (node (ref "R69") (pin "2") (pinfunction "2_2") (pintype "passive"))
    )
    (net (code "124") (name "Net-(D5-RED)") (class "Default")
      (node (ref "D5") (pin "1") (pinfunction "RED_1") (pintype "passive"))
      (node (ref "R70") (pin "1") (pinfunction "1_1") (pintype "passive"))
    )
    (net (code "125") (name "Net-(U5-IN+)") (class "Default")
      (node (ref "R71") (pin "2") (pinfunction "2_2") (pintype "passive"))
      (node (ref "R72") (pin "1") (pinfunction "1_1") (pintype "passive"))
      (node (ref "U5") (pin "3") (pinfunction "IN+_3") (pintype "input"))
    )
    (net (code "126") (name "Net-(Y1-OSC1)") (class "Default")
      (node (ref "C12") (pin "1") (pinfunction "1_1") (pintype "passive"))
      (node (ref "R4") (pin "1") (pinfunction "1_1") (pintype "passive"))
      (node (ref "Y1") (pin "1") (pinfunction "OSC1_1") (pintype "passive"))
    )
    (net (code "127") (name "Vin") (class "Default")
      (node (ref "C1") (pin "2") (pinfunction "2_2") (pintype "passive"))
      (node (ref "C25") (pin "2") (pinfunction "2_2") (pintype "passive"))
      (node (ref "C3") (pin "2") (pinfunction "2_2") (pintype "passive"))
      (node (ref "D1") (pin "1") (pinfunction "K_1") (pintype "passive"))
      (node (ref "D2") (pin "1") (pinfunction "K_1") (pintype "passive"))
      (node (ref "D6") (pin "3") (pinfunction "K_3") (pintype "passive"))
      (node (ref "J1") (pin "11") (pinfunction "11_11") (pintype "power_in"))
      (node (ref "J1") (pin "12") (pinfunction "12_12") (pintype "power_in"))
      (node (ref "J1") (pin "13") (pinfunction "13_13") (pintype "power_in"))
      (node (ref "J1") (pin "14") (pinfunction "14_14") (pintype "power_in"))
      (node (ref "J1") (pin "15") (pinfunction "15_15") (pintype "power_in"))
      (node (ref "J1") (pin "16") (pinfunction "16_16") (pintype "power_in"))
      (node (ref "J1") (pin "17") (pinfunction "17_17") (pintype "power_in"))
      (node (ref "J1") (pin "18") (pinfunction "18_18") (pintype "power_in"))
      (node (ref "J1") (pin "19") (pinfunction "19_19") (pintype "power_in"))
      (node (ref "J1") (pin "20") (pinfunction "20_20") (pintype "power_in"))
      (node (ref "J2") (pin "11") (pinfunction "11_11") (pintype "power_in"))
      (node (ref "J2") (pin "12") (pinfunction "12_12") (pintype "power_in"))
      (node (ref "J2") (pin "13") (pinfunction "13_13") (pintype "power_in"))
      (node (ref "J2") (pin "14") (pinfunction "14_14") (pintype "power_in"))
      (node (ref "J2") (pin "15") (pinfunction "15_15") (pintype "power_in"))
      (node (ref "J2") (pin "16") (pinfunction "16_16") (pintype "power_in"))
      (node (ref "J2") (pin "17") (pinfunction "17_17") (pintype "power_in"))
      (node (ref "J2") (pin "18") (pinfunction "18_18") (pintype "power_in"))
      (node (ref "J2") (pin "19") (pinfunction "19_19") (pintype "power_in"))
      (node (ref "J2") (pin "20") (pinfunction "20_20") (pintype "power_in"))
      (node (ref "J3") (pin "10") (pinfunction "10_10") (pintype "power_in"))
      (node (ref "J3") (pin "11") (pinfunction "11_11") (pintype "power_in"))
      (node (ref "J3") (pin "12") (pinfunction "12_12") (pintype "power_in"))
      (node (ref "J3") (pin "13") (pinfunction "13_13") (pintype "power_in"))
      (node (ref "J3") (pin "14") (pinfunction "14_14") (pintype "power_in"))
      (node (ref "J3") (pin "15") (pinfunction "15_15") (pintype "power_in"))
      (node (ref "J3") (pin "16") (pinfunction "16_16") (pintype "power_in"))
      (node (ref "J3") (pin "17") (pinfunction "17_17") (pintype "power_in"))
      (node (ref "J3") (pin "18") (pinfunction "18_18") (pintype "power_in"))
      (node (ref "J4") (pin "10") (pinfunction "10_10") (pintype "power_in"))
      (node (ref "J4") (pin "11") (pinfunction "11_11") (pintype "power_in"))
      (node (ref "J4") (pin "12") (pinfunction "12_12") (pintype "power_in"))
      (node (ref "J4") (pin "13") (pinfunction "13_13") (pintype "power_in"))
      (node (ref "J4") (pin "14") (pinfunction "14_14") (pintype "power_in"))
      (node (ref "J4") (pin "15") (pinfunction "15_15") (pintype "power_in"))
      (node (ref "J4") (pin "16") (pinfunction "16_16") (pintype "power_in"))
      (node (ref "J4") (pin "17") (pinfunction "17_17") (pintype "power_in"))
      (node (ref "J4") (pin "18") (pinfunction "18_18") (pintype "power_in"))
      (node (ref "J5") (pin "10") (pinfunction "10_10") (pintype "power_in"))
      (node (ref "J5") (pin "11") (pinfunction "11_11") (pintype "power_in"))
      (node (ref "J5") (pin "12") (pinfunction "12_12") (pintype "power_in"))
      (node (ref "J5") (pin "13") (pinfunction "13_13") (pintype "power_in"))
      (node (ref "J5") (pin "14") (pinfunction "14_14") (pintype "power_in"))
      (node (ref "J5") (pin "15") (pinfunction "15_15") (pintype "power_in"))
      (node (ref "J5") (pin "16") (pinfunction "16_16") (pintype "power_in"))
      (node (ref "J5") (pin "9") (pinfunction "9_9") (pintype "power_in"))
      (node (ref "J6") (pin "10") (pinfunction "10_10") (pintype "power_in"))
      (node (ref "J6") (pin "11") (pinfunction "11_11") (pintype "power_in"))
      (node (ref "J6") (pin "12") (pinfunction "12_12") (pintype "power_in"))
      (node (ref "J6") (pin "13") (pinfunction "13_13") (pintype "power_in"))
      (node (ref "J6") (pin "14") (pinfunction "14_14") (pintype "power_in"))
      (node (ref "J6") (pin "15") (pinfunction "15_15") (pintype "power_in"))
      (node (ref "J6") (pin "16") (pinfunction "16_16") (pintype "power_in"))
      (node (ref "J6") (pin "9") (pinfunction "9_9") (pintype "power_in"))
      (node (ref "J9") (pin "1") (pinfunction "1_1") (pintype "power_in"))
      (node (ref "R71") (pin "1") (pinfunction "1_1") (pintype "passive"))
      (node (ref "U2") (pin "1") (pinfunction "Vin_1") (pintype "passive"))
      (node (ref "U2") (pin "3") (pinfunction "EN_3") (pintype "passive"))
      (node (ref "U3") (pin "1") (pinfunction "Vin_1") (pintype "passive"))
      (node (ref "U3") (pin "3") (pinfunction "EN_3") (pintype "passive"))
    )
    (net (code "128") (name "unconnected-(J7-Pad6)") (class "Default")
      (node (ref "J7") (pin "6") (pinfunction "6_6") (pintype "passive"))
    )
    (net (code "129") (name "unconnected-(J7-Pad7)") (class "Default")
      (node (ref "J7") (pin "7") (pinfunction "7_7") (pintype "passive"))
    )
    (net (code "130") (name "unconnected-(J7-Pad8)") (class "Default")
      (node (ref "J7") (pin "8") (pinfunction "8_8") (pintype "output"))
    )
    (net (code "131") (name "unconnected-(U1-PB8-Pad61)") (class "Default")
      (node (ref "U1") (pin "61") (pinfunction "PB8_61") (pintype "power_in"))
    )
    (net (code "132") (name "unconnected-(U1-PB9-Pad62)") (class "Default")
      (node (ref "U1") (pin "62") (pinfunction "PB9_62") (pintype "power_in"))
    )
    (net (code "133") (name "unconnected-(U1-PC2-Pad10)") (class "Default")
      (node (ref "U1") (pin "10") (pinfunction "PC2_10") (pintype "power_in"))
    )
    (net (code "134") (name "unconnected-(U1-PF4-Pad18)") (class "Default")
      (node (ref "U1") (pin "18") (pinfunction "PF4_18") (pintype "power_in"))
    )
    (net (code "135") (name "unconnected-(U2-NC-Pad4)") (class "Default")
      (node (ref "U2") (pin "4") (pinfunction "NC_4") (pintype "passive"))
    )
    (net (code "136") (name "unconnected-(U3-NC-Pad4)") (class "Default")
      (node (ref "U3") (pin "4") (pinfunction "NC_4") (pintype "passive"))
    )
  )
)
